# MicroControllerSTM32f103.net
KiCad netlist of a schematic drawn in Altium Designer
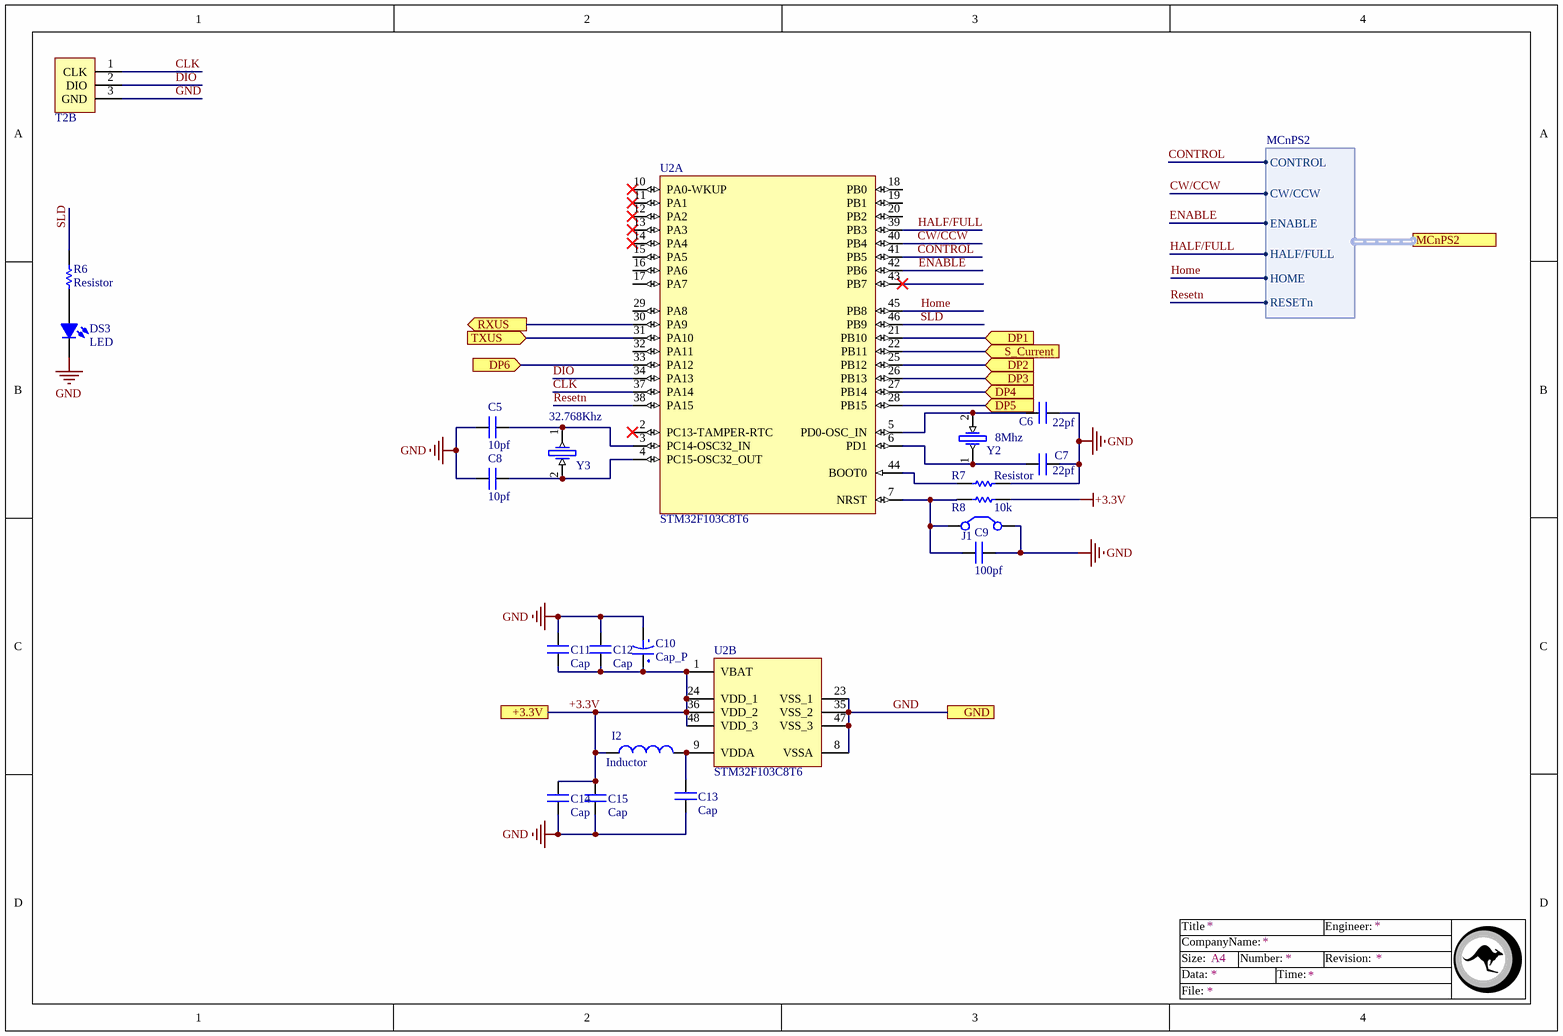
[diagram p0: MicroControllerSTM32f103.SchDoc]

(export (version "E")
  (design (tool "Eeschema 10.0.6"))
  (components
    (comp (ref "C5")
      (value "10pf")
      (footprint "Cap0805")
      (description "Surface mount Capacitor")
      (libsource (lib "PMLIB2020") (part "Cap"))
    )
    (comp (ref "C6")
      (value "22pf")
      (footprint "Cap0805")
      (description "Surface mount Capacitor")
      (libsource (lib "PMLIB2020") (part "Cap"))
    )
    (comp (ref "C7")
      (value "22pf")
      (footprint "Cap0805")
      (description "Surface mount Capacitor")
      (libsource (lib "PMLIB2020") (part "Cap"))
    )
    (comp (ref "C8")
      (value "10pf")
      (footprint "Cap0805")
      (description "Surface mount Capacitor")
      (libsource (lib "PMLIB2020") (part "Cap"))
    )
    (comp (ref "C9")
      (value "100pf")
      (footprint "Cap0805")
      (description "Surface mount Capacitor")
      (libsource (lib "PMLIB2020") (part "Cap"))
    )
    (comp (ref "C10")
      (value "Cap_P")
      (footprint "CAPMOL_C")
      (description "Polarity")
      (libsource (lib "PMLIB2020") (part "Cap_P"))
    )
    (comp (ref "C11")
      (value "Cap")
      (footprint "Cap0805")
      (description "Surface mount Capacitor")
      (libsource (lib "PMLIB2020") (part "Cap"))
    )
    (comp (ref "C12")
      (value "Cap")
      (footprint "Cap0805")
      (description "Surface mount Capacitor")
      (libsource (lib "PMLIB2020") (part "Cap"))
    )
    (comp (ref "C13")
      (value "Cap")
      (footprint "Cap0805")
      (description "Surface mount Capacitor")
      (libsource (lib "PMLIB2020") (part "Cap"))
    )
    (comp (ref "C14")
      (value "Cap")
      (footprint "Cap0805")
      (description "Surface mount Capacitor")
      (libsource (lib "PMLIB2020") (part "Cap"))
    )
    (comp (ref "C15")
      (value "Cap")
      (footprint "Cap0805")
      (description "Surface mount Capacitor")
      (libsource (lib "PMLIB2020") (part "Cap"))
    )
    (comp (ref "DS3") (value "LED") (footprint "Led0805") (libsource (lib "PMLIB2020") (part "LED")))
    (comp (ref "I2")
      (value "Inductor")
      (footprint "1206")
      (description "Indicator")
      (libsource (lib "PMLIB2020") (part "Inductor"))
    )
    (comp (ref "J1")
      (value "Jumper")
      (footprint "Jumper SMD - Small")
      (libsource (lib "PMLIB2020") (part "Jumper"))
    )
    (comp (ref "R6") (value "Resistor") (footprint "R0805") (libsource (lib "PMLIB2020") (part "Resistor")))
    (comp (ref "R7") (value "Resistor") (footprint "R0805") (libsource (lib "PMLIB2020") (part "Resistor")))
    (comp (ref "R8")
      (value "10k")
      (footprint "R0805")
      (description "Resistor")
      (libsource (lib "PMLIB2020") (part "Resistor"))
    )
    (comp (ref "T2")
      (value "Serial Program")
      (footprint "MHDR1X03-254P - E")
      (description "STM Serial Program pin")
      (libsource (lib "PMLIB2020") (part "Serial Program"))
    )
    (comp (ref "U2")
      (value "STM32F103C8T6")
      (footprint "LQFP48_L")
      (libsource (lib "STMicroelectronics STM32 F1") (part "STM32F103C8T6"))
    )
    (comp (ref "Y2")
      (value "8Mhz")
      (footprint "CrystallB")
      (description "Crystal")
      (libsource (lib "") (part "Crystal_1"))
    )
    (comp (ref "Y3")
      (value "32.768Khz")
      (footprint "CrystallB")
      (description "Crystal")
      (libsource (lib "PMLIB2020") (part "Crystal"))
    )
  )
  (nets
    (net (code "2") (name "+3.3V") (class "Default")
      (node (ref "C10") (pin "2") (pinfunction "2_2") (pintype "passive"))
      (node (ref "C11") (pin "1") (pinfunction "1_1") (pintype "passive"))
      (node (ref "C12") (pin "1") (pinfunction "1_1") (pintype "passive"))
      (node (ref "C14") (pin "2") (pinfunction "2_2") (pintype "passive"))
      (node (ref "C15") (pin "2") (pinfunction "2_2") (pintype "passive"))
      (node (ref "I2") (pin "1") (pinfunction "1_1") (pintype "passive"))
      (node (ref "R8") (pin "1") (pinfunction "1_1") (pintype "passive"))
      (node (ref "U2") (pin "1") (pinfunction "VBAT_1") (pintype "power_in"))
      (node (ref "U2") (pin "24") (pinfunction "VDD_1_24") (pintype "power_in"))
      (node (ref "U2") (pin "36") (pinfunction "VDD_2_36") (pintype "power_in"))
      (node (ref "U2") (pin "48") (pinfunction "VDD_3_48") (pintype "power_in"))
    )
    (net (code "3") (name "/CLK") (class "Default")
      (node (ref "T2") (pin "1") (pinfunction "CLK_1") (pintype "passive"))
      (node (ref "U2") (pin "37") (pinfunction "PA14_37") (pintype "bidirectional"))
    )
    (net (code "4") (name "/CONTROL") (class "Default")
      (node (ref "U2") (pin "41") (pinfunction "PB5_41") (pintype "bidirectional"))
    )
    (net (code "5") (name "/CW{slash}CCW") (class "Default")
      (node (ref "U2") (pin "40") (pinfunction "PB4_40") (pintype "bidirectional"))
    )
    (net (code "6") (name "/DIO") (class "Default")
      (node (ref "T2") (pin "2") (pinfunction "DIO_2") (pintype "passive"))
      (node (ref "U2") (pin "34") (pinfunction "PA13_34") (pintype "bidirectional"))
    )
    (net (code "7") (name "/DP1") (class "Default")
      (node (ref "U2") (pin "21") (pinfunction "PB10_21") (pintype "bidirectional"))
    )
    (net (code "8") (name "/DP2") (class "Default")
      (node (ref "U2") (pin "25") (pinfunction "PB12_25") (pintype "bidirectional"))
    )
    (net (code "9") (name "/DP3") (class "Default")
      (node (ref "U2") (pin "26") (pinfunction "PB13_26") (pintype "bidirectional"))
    )
    (net (code "10") (name "/DP4") (class "Default")
      (node (ref "U2") (pin "27") (pinfunction "PB14_27") (pintype "bidirectional"))
    )
    (net (code "11") (name "/DP5") (class "Default")
      (node (ref "U2") (pin "28") (pinfunction "PB15_28") (pintype "bidirectional"))
    )
    (net (code "12") (name "/DP6") (class "Default")
      (node (ref "U2") (pin "33") (pinfunction "PA12_33") (pintype "bidirectional"))
    )
    (net (code "13") (name "/ENABLE") (class "Default")
      (node (ref "U2") (pin "42") (pinfunction "PB6_42") (pintype "bidirectional"))
    )
    (net (code "14") (name "/HALF{slash}FULL") (class "Default")
      (node (ref "U2") (pin "39") (pinfunction "PB3_39") (pintype "bidirectional"))
    )
    (net (code "15") (name "/Home") (class "Default")
      (node (ref "U2") (pin "45") (pinfunction "PB8_45") (pintype "bidirectional"))
    )
    (net (code "16") (name "/RXUS") (class "Default")
      (node (ref "U2") (pin "30") (pinfunction "PA9_30") (pintype "bidirectional"))
    )
    (net (code "17") (name "/Resetn") (class "Default")
      (node (ref "U2") (pin "38") (pinfunction "PA15_38") (pintype "bidirectional"))
    )
    (net (code "18") (name "/SLD") (class "Default")
      (node (ref "R6") (pin "1") (pinfunction "1_1") (pintype "passive"))
      (node (ref "U2") (pin "46") (pinfunction "PB9_46") (pintype "bidirectional"))
    )
    (net (code "19") (name "/S_Current") (class "Default")
      (node (ref "U2") (pin "22") (pinfunction "PB11_22") (pintype "bidirectional"))
    )
    (net (code "20") (name "/TXUS") (class "Default")
      (node (ref "U2") (pin "31") (pinfunction "PA10_31") (pintype "bidirectional"))
    )
    (net (code "22") (name "GND") (class "Default")
      (node (ref "C10") (pin "1") (pinfunction "1_1") (pintype "passive"))
      (node (ref "C11") (pin "2") (pinfunction "2_2") (pintype "passive"))
      (node (ref "C12") (pin "2") (pinfunction "2_2") (pintype "passive"))
      (node (ref "C13") (pin "1") (pinfunction "1_1") (pintype "passive"))
      (node (ref "C14") (pin "1") (pinfunction "1_1") (pintype "passive"))
      (node (ref "C15") (pin "1") (pinfunction "1_1") (pintype "passive"))
      (node (ref "C5") (pin "1") (pinfunction "1_1") (pintype "passive"))
      (node (ref "C6") (pin "1") (pinfunction "1_1") (pintype "passive"))
      (node (ref "C7") (pin "1") (pinfunction "1_1") (pintype "passive"))
      (node (ref "C8") (pin "1") (pinfunction "1_1") (pintype "passive"))
      (node (ref "C9") (pin "2") (pinfunction "2_2") (pintype "passive"))
      (node (ref "DS3") (pin "K") (pinfunction "K_K") (pintype "passive"))
      (node (ref "J1") (pin "2") (pinfunction "C2_2") (pintype "passive"))
      (node (ref "R7") (pin "2") (pinfunction "2_2") (pintype "passive"))
      (node (ref "T2") (pin "3") (pinfunction "GND_3") (pintype "passive"))
      (node (ref "U2") (pin "23") (pinfunction "VSS_1_23") (pintype "power_in"))
      (node (ref "U2") (pin "35") (pinfunction "VSS_2_35") (pintype "power_in"))
      (node (ref "U2") (pin "47") (pinfunction "VSS_3_47") (pintype "power_in"))
      (node (ref "U2") (pin "8") (pinfunction "VSSA_8") (pintype "power_in"))
    )
    (net (code "23") (name "Net-(DS3-PadA)") (class "Default")
      (node (ref "DS3") (pin "A") (pinfunction "A_A") (pintype "passive"))
      (node (ref "R6") (pin "2") (pinfunction "2_2") (pintype "passive"))
    )
    (net (code "24") (name "Net-(J1-C1)") (class "Default")
      (node (ref "C9") (pin "1") (pinfunction "1_1") (pintype "passive"))
      (node (ref "J1") (pin "1") (pinfunction "C1_1") (pintype "passive"))
      (node (ref "R8") (pin "2") (pinfunction "2_2") (pintype "passive"))
      (node (ref "U2") (pin "7") (pinfunction "NRST_7") (pintype "bidirectional"))
    )
    (net (code "25") (name "Net-(U2A-BOOT0)") (class "Default")
      (node (ref "R7") (pin "1") (pinfunction "1_1") (pintype "passive"))
      (node (ref "U2") (pin "44") (pinfunction "BOOT0_44") (pintype "input"))
    )
    (net (code "26") (name "Net-(U2A-PC14-OSC32_IN)") (class "Default")
      (node (ref "C5") (pin "2") (pinfunction "2_2") (pintype "passive"))
      (node (ref "U2") (pin "3") (pinfunction "PC14-OSC32_IN_3") (pintype "bidirectional"))
      (node (ref "Y3") (pin "1") (pinfunction "1_1") (pintype "output"))
    )
    (net (code "27") (name "Net-(U2A-PC15-OSC32_OUT)") (class "Default")
      (node (ref "C8") (pin "2") (pinfunction "2_2") (pintype "passive"))
      (node (ref "U2") (pin "4") (pinfunction "PC15-OSC32_OUT_4") (pintype "bidirectional"))
      (node (ref "Y3") (pin "2") (pinfunction "2_2") (pintype "input"))
    )
    (net (code "28") (name "Net-(U2A-PD0-OSC_IN)") (class "Default")
      (node (ref "C6") (pin "2") (pinfunction "2_2") (pintype "passive"))
      (node (ref "U2") (pin "5") (pinfunction "PD0-OSC_IN_5") (pintype "bidirectional"))
      (node (ref "Y2") (pin "2") (pinfunction "2_2") (pintype "input"))
    )
    (net (code "29") (name "Net-(U2A-PD1)") (class "Default")
      (node (ref "C7") (pin "2") (pinfunction "2_2") (pintype "passive"))
      (node (ref "U2") (pin "6") (pinfunction "PD1_6") (pintype "bidirectional"))
      (node (ref "Y2") (pin "1") (pinfunction "1_1") (pintype "output"))
    )
    (net (code "30") (name "Net-(U2B-VDDA)") (class "Default")
      (node (ref "C13") (pin "2") (pinfunction "2_2") (pintype "passive"))
      (node (ref "I2") (pin "2") (pinfunction "2_2") (pintype "passive"))
      (node (ref "U2") (pin "9") (pinfunction "VDDA_9") (pintype "power_in"))
    )
    (net (code "31") (name "unconnected-(U2A-PA0-WKUP-Pad10)") (class "Default")
      (node (ref "U2") (pin "10") (pinfunction "PA0-WKUP_10") (pintype "bidirectional+no_connect"))
    )
    (net (code "32") (name "unconnected-(U2A-PA1-Pad11)") (class "Default")
      (node (ref "U2") (pin "11") (pinfunction "PA1_11") (pintype "bidirectional+no_connect"))
    )
    (net (code "33") (name "unconnected-(U2A-PA2-Pad12)") (class "Default")
      (node (ref "U2") (pin "12") (pinfunction "PA2_12") (pintype "bidirectional+no_connect"))
    )
    (net (code "34") (name "unconnected-(U2A-PA3-Pad13)") (class "Default")
      (node (ref "U2") (pin "13") (pinfunction "PA3_13") (pintype "bidirectional+no_connect"))
    )
    (net (code "35") (name "unconnected-(U2A-PA4-Pad14)") (class "Default")
      (node (ref "U2") (pin "14") (pinfunction "PA4_14") (pintype "bidirectional+no_connect"))
    )
    (net (code "36") (name "unconnected-(U2A-PA5-Pad15)") (class "Default")
      (node (ref "U2") (pin "15") (pinfunction "PA5_15") (pintype "bidirectional"))
    )
    (net (code "37") (name "unconnected-(U2A-PA6-Pad16)") (class "Default")
      (node (ref "U2") (pin "16") (pinfunction "PA6_16") (pintype "bidirectional"))
    )
    (net (code "38") (name "unconnected-(U2A-PA7-Pad17)") (class "Default")
      (node (ref "U2") (pin "17") (pinfunction "PA7_17") (pintype "bidirectional"))
    )
    (net (code "39") (name "unconnected-(U2A-PA8-Pad29)") (class "Default")
      (node (ref "U2") (pin "29") (pinfunction "PA8_29") (pintype "bidirectional"))
    )
    (net (code "40") (name "unconnected-(U2A-PA11-Pad32)") (class "Default")
      (node (ref "U2") (pin "32") (pinfunction "PA11_32") (pintype "bidirectional"))
    )
    (net (code "41") (name "unconnected-(U2A-PB0-Pad18)") (class "Default")
      (node (ref "U2") (pin "18") (pinfunction "PB0_18") (pintype "bidirectional"))
    )
    (net (code "42") (name "unconnected-(U2A-PB1-Pad19)") (class "Default")
      (node (ref "U2") (pin "19") (pinfunction "PB1_19") (pintype "bidirectional"))
    )
    (net (code "43") (name "unconnected-(U2A-PB2-Pad20)") (class "Default")
      (node (ref "U2") (pin "20") (pinfunction "PB2_20") (pintype "bidirectional"))
    )
    (net (code "44") (name "unconnected-(U2A-PB7-Pad43)") (class "Default")
      (node (ref "U2") (pin "43") (pinfunction "PB7_43") (pintype "bidirectional+no_connect"))
    )
    (net (code "45") (name "unconnected-(U2A-PC13-TAMPER-RTC-Pad2)") (class "Default")
      (node (ref "U2") (pin "2") (pinfunction "PC13-TAMPER-RTC_2") (pintype "bidirectional+no_connect"))
    )
  )
)
